# NusbioMCU_NeoPixels.net
KiCad netlist of a schematic drawn in EAGLE
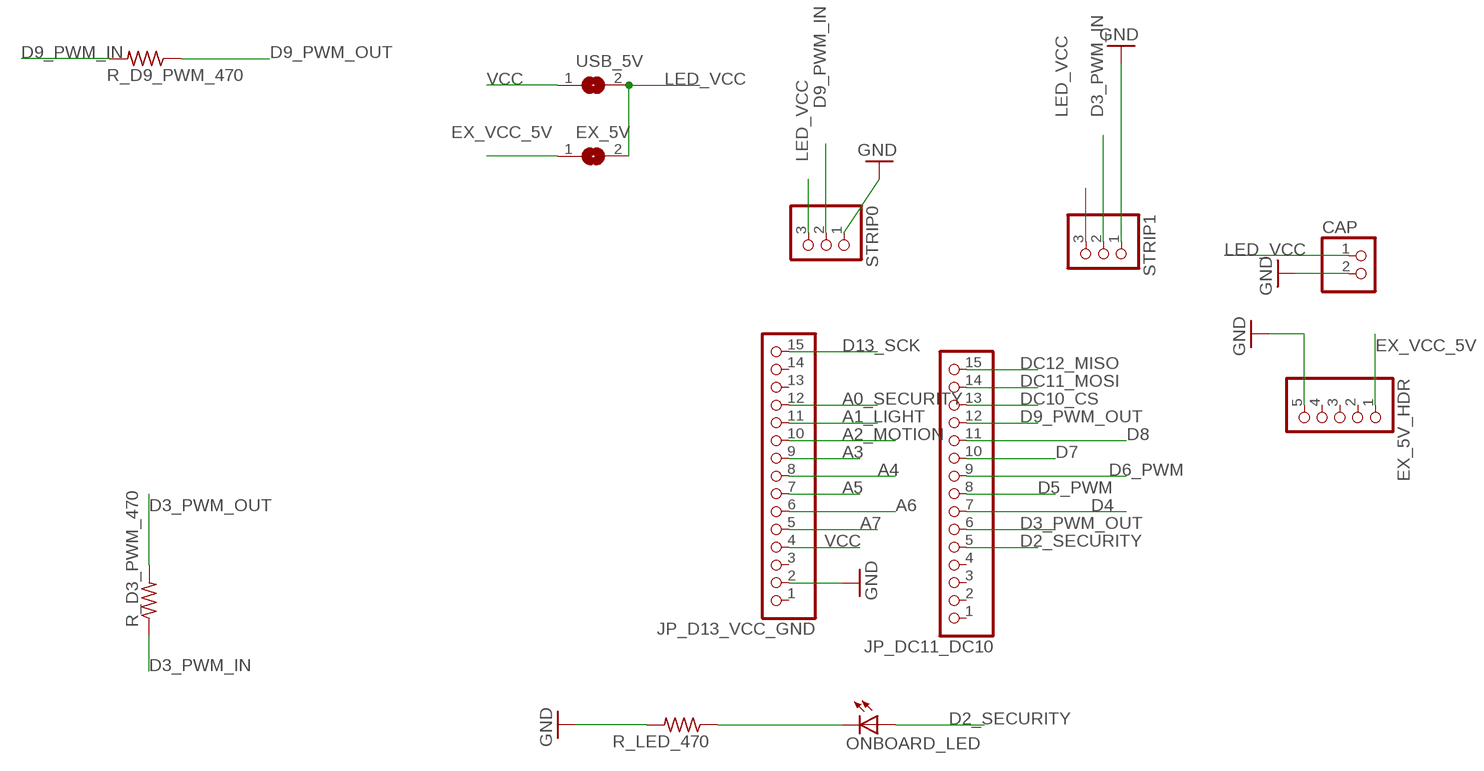
[diagram p0: schematic, sheet 1]

(export (version "E")
  (design (tool "Eeschema 10.0.6"))
  (components
    (comp (ref "CAP")
      (value "PINHD-1X2")
      (footprint "eagle-import:1X02")
      (libsource (lib "eagle-import") (part "PINHD-1X2"))
    )
    (comp (ref "EX_5V")
      (value "SOLDERJUMPERREFLOW")
      (footprint "eagle-import:SOLDERJUMPER_REFLOW")
      (libsource (lib "eagle-import") (part "SOLDERJUMPERREFLOW"))
    )
    (comp (ref "EX_5V_HDR")
      (value "PINHD-1X5")
      (footprint "eagle-import:1X05")
      (libsource (lib "eagle-import") (part "PINHD-1X5"))
    )
    (comp (ref "JP_D13_VCC_GND")
      (value "PINHD-1X15")
      (footprint "eagle-import:1X15")
      (libsource (lib "eagle-import") (part "PINHD-1X15"))
    )
    (comp (ref "JP_DC11_DC10")
      (value "PINHD-1X15")
      (footprint "eagle-import:1X15")
      (libsource (lib "eagle-import") (part "PINHD-1X15"))
    )
    (comp (ref "ONBOARD_LED")
      (value "LEDSMT1206")
      (footprint "eagle-import:1206")
      (libsource (lib "eagle-import") (part "LEDSMT1206"))
    )
    (comp (ref "R_D3_PWM_470")
      (value "R-US_R1206")
      (footprint "eagle-import:R1206")
      (libsource (lib "eagle-import") (part "R-US_R1206"))
    )
    (comp (ref "R_D9_PWM_470")
      (value "R-US_R1206")
      (footprint "eagle-import:R1206")
      (libsource (lib "eagle-import") (part "R-US_R1206"))
    )
    (comp (ref "R_LED_470")
      (value "R-US_R1206")
      (footprint "eagle-import:R1206")
      (libsource (lib "eagle-import") (part "R-US_R1206"))
    )
    (comp (ref "STRIP0")
      (value "PINHD-1X3")
      (footprint "eagle-import:1X03")
      (libsource (lib "eagle-import") (part "PINHD-1X3"))
    )
    (comp (ref "STRIP1")
      (value "PINHD-1X3")
      (footprint "eagle-import:1X03")
      (libsource (lib "eagle-import") (part "PINHD-1X3"))
    )
    (comp (ref "USB_5V")
      (value "SOLDERJUMPERREFLOW")
      (footprint "eagle-import:SOLDERJUMPER_REFLOW")
      (libsource (lib "eagle-import") (part "SOLDERJUMPERREFLOW"))
    )
  )
  (nets
    (net (code "1") (name "/A0_SECURITY") (class "Default")
      (node (ref "JP_D13_VCC_GND") (pin "12") (pinfunction "12_12") (pintype "passive"))
    )
    (net (code "2") (name "/A1_LIGHT") (class "Default")
      (node (ref "JP_D13_VCC_GND") (pin "11") (pinfunction "11_11") (pintype "passive"))
    )
    (net (code "3") (name "/A2_MOTION") (class "Default")
      (node (ref "JP_D13_VCC_GND") (pin "10") (pinfunction "10_10") (pintype "passive"))
    )
    (net (code "4") (name "/A3") (class "Default")
      (node (ref "JP_D13_VCC_GND") (pin "9") (pinfunction "9_9") (pintype "passive"))
    )
    (net (code "5") (name "/A4") (class "Default")
      (node (ref "JP_D13_VCC_GND") (pin "8") (pinfunction "8_8") (pintype "passive"))
    )
    (net (code "6") (name "/A5") (class "Default")
      (node (ref "JP_D13_VCC_GND") (pin "7") (pinfunction "7_7") (pintype "passive"))
    )
    (net (code "7") (name "/A6") (class "Default")
      (node (ref "JP_D13_VCC_GND") (pin "6") (pinfunction "6_6") (pintype "passive"))
    )
    (net (code "8") (name "/A7") (class "Default")
      (node (ref "JP_D13_VCC_GND") (pin "5") (pinfunction "5_5") (pintype "passive"))
    )
    (net (code "9") (name "/D2_SECURITY") (class "Default")
      (node (ref "JP_DC11_DC10") (pin "5") (pinfunction "5_5") (pintype "passive"))
      (node (ref "ONBOARD_LED") (pin "A") (pinfunction "A_A") (pintype "passive"))
    )
    (net (code "10") (name "/D3_PWM_IN") (class "Default")
      (node (ref "R_D3_PWM_470") (pin "1") (pinfunction "1_1") (pintype "passive"))
      (node (ref "STRIP1") (pin "2") (pinfunction "2_2") (pintype "passive"))
    )
    (net (code "11") (name "/D3_PWM_OUT") (class "Default")
      (node (ref "JP_DC11_DC10") (pin "6") (pinfunction "6_6") (pintype "passive"))
      (node (ref "R_D3_PWM_470") (pin "2") (pinfunction "2_2") (pintype "passive"))
    )
    (net (code "12") (name "/D4") (class "Default")
      (node (ref "JP_DC11_DC10") (pin "7") (pinfunction "7_7") (pintype "passive"))
    )
    (net (code "13") (name "/D5_PWM") (class "Default")
      (node (ref "JP_DC11_DC10") (pin "8") (pinfunction "8_8") (pintype "passive"))
    )
    (net (code "14") (name "/D6_PWM") (class "Default")
      (node (ref "JP_DC11_DC10") (pin "9") (pinfunction "9_9") (pintype "passive"))
    )
    (net (code "15") (name "/D7") (class "Default")
      (node (ref "JP_DC11_DC10") (pin "10") (pinfunction "10_10") (pintype "passive"))
    )
    (net (code "16") (name "/D8") (class "Default")
      (node (ref "JP_DC11_DC10") (pin "11") (pinfunction "11_11") (pintype "passive"))
    )
    (net (code "17") (name "/D9_PWM_IN") (class "Default")
      (node (ref "R_D9_PWM_470") (pin "2") (pinfunction "2_2") (pintype "passive"))
      (node (ref "STRIP0") (pin "2") (pinfunction "2_2") (pintype "passive"))
    )
    (net (code "18") (name "/D9_PWM_OUT") (class "Default")
      (node (ref "JP_DC11_DC10") (pin "12") (pinfunction "12_12") (pintype "passive"))
      (node (ref "R_D9_PWM_470") (pin "1") (pinfunction "1_1") (pintype "passive"))
    )
    (net (code "19") (name "/D13_SCK") (class "Default")
      (node (ref "JP_D13_VCC_GND") (pin "15") (pinfunction "15_15") (pintype "passive"))
    )
    (net (code "20") (name "/DC10_CS") (class "Default")
      (node (ref "JP_DC11_DC10") (pin "13") (pinfunction "13_13") (pintype "passive"))
    )
    (net (code "21") (name "/DC11_MOSI") (class "Default")
      (node (ref "JP_DC11_DC10") (pin "14") (pinfunction "14_14") (pintype "passive"))
    )
    (net (code "22") (name "/DC12_MISO") (class "Default")
      (node (ref "JP_DC11_DC10") (pin "15") (pinfunction "15_15") (pintype "passive"))
    )
    (net (code "23") (name "/EX_VCC_5V") (class "Default")
      (node (ref "EX_5V") (pin "1") (pinfunction "1_1") (pintype "passive"))
      (node (ref "EX_5V_HDR") (pin "1") (pinfunction "1_1") (pintype "passive"))
    )
    (net (code "24") (name "/LED_VCC") (class "Default")
      (node (ref "CAP") (pin "1") (pinfunction "1_1") (pintype "passive"))
      (node (ref "EX_5V") (pin "2") (pinfunction "2_2") (pintype "passive"))
      (node (ref "STRIP0") (pin "3") (pinfunction "3_3") (pintype "passive"))
      (node (ref "STRIP1") (pin "3") (pinfunction "3_3") (pintype "passive"))
      (node (ref "USB_5V") (pin "2") (pinfunction "2_2") (pintype "passive"))
    )
    (net (code "25") (name "/VCC") (class "Default")
      (node (ref "JP_D13_VCC_GND") (pin "4") (pinfunction "4_4") (pintype "passive"))
      (node (ref "USB_5V") (pin "1") (pinfunction "1_1") (pintype "passive"))
    )
    (net (code "26") (name "GND") (class "Default")
      (node (ref "CAP") (pin "2") (pinfunction "2_2") (pintype "passive"))
      (node (ref "EX_5V_HDR") (pin "5") (pinfunction "5_5") (pintype "passive"))
      (node (ref "JP_D13_VCC_GND") (pin "2") (pinfunction "2_2") (pintype "passive"))
      (node (ref "R_LED_470") (pin "2") (pinfunction "2_2") (pintype "passive"))
      (node (ref "STRIP0") (pin "1") (pinfunction "1_1") (pintype "passive"))
      (node (ref "STRIP1") (pin "1") (pinfunction "1_1") (pintype "passive"))
    )
    (net (code "27") (name "Net-(ONBOARD_LED-PadC)") (class "Default")
      (node (ref "ONBOARD_LED") (pin "C") (pinfunction "C_C") (pintype "passive"))
      (node (ref "R_LED_470") (pin "1") (pinfunction "1_1") (pintype "passive"))
    )
    (net (code "28") (name "unconnected-(EX_5V_HDR-Pad2)") (class "Default")
      (node (ref "EX_5V_HDR") (pin "2") (pinfunction "2_2") (pintype "passive"))
    )
    (net (code "29") (name "unconnected-(EX_5V_HDR-Pad3)") (class "Default")
      (node (ref "EX_5V_HDR") (pin "3") (pinfunction "3_3") (pintype "passive"))
    )
    (net (code "30") (name "unconnected-(EX_5V_HDR-Pad4)") (class "Default")
      (node (ref "EX_5V_HDR") (pin "4") (pinfunction "4_4") (pintype "passive"))
    )
    (net (code "31") (name "unconnected-(JP_D13_VCC_GND-Pad1)") (class "Default")
      (node (ref "JP_D13_VCC_GND") (pin "1") (pinfunction "1_1") (pintype "passive"))
    )
    (net (code "32") (name "unconnected-(JP_D13_VCC_GND-Pad3)") (class "Default")
      (node (ref "JP_D13_VCC_GND") (pin "3") (pinfunction "3_3") (pintype "passive"))
    )
    (net (code "33") (name "unconnected-(JP_D13_VCC_GND-Pad13)") (class "Default")
      (node (ref "JP_D13_VCC_GND") (pin "13") (pinfunction "13_13") (pintype "passive"))
    )
    (net (code "34") (name "unconnected-(JP_D13_VCC_GND-Pad14)") (class "Default")
      (node (ref "JP_D13_VCC_GND") (pin "14") (pinfunction "14_14") (pintype "passive"))
    )
    (net (code "35") (name "unconnected-(JP_DC11_DC10-Pad1)") (class "Default")
      (node (ref "JP_DC11_DC10") (pin "1") (pinfunction "1_1") (pintype "passive"))
    )
    (net (code "36") (name "unconnected-(JP_DC11_DC10-Pad2)") (class "Default")
      (node (ref "JP_DC11_DC10") (pin "2") (pinfunction "2_2") (pintype "passive"))
    )
    (net (code "37") (name "unconnected-(JP_DC11_DC10-Pad3)") (class "Default")
      (node (ref "JP_DC11_DC10") (pin "3") (pinfunction "3_3") (pintype "passive"))
    )
    (net (code "38") (name "unconnected-(JP_DC11_DC10-Pad4)") (class "Default")
      (node (ref "JP_DC11_DC10") (pin "4") (pinfunction "4_4") (pintype "passive"))
    )
  )
)
